# Holder_Accu.net
KiCad netlist of a schematic drawn in Altium Designer
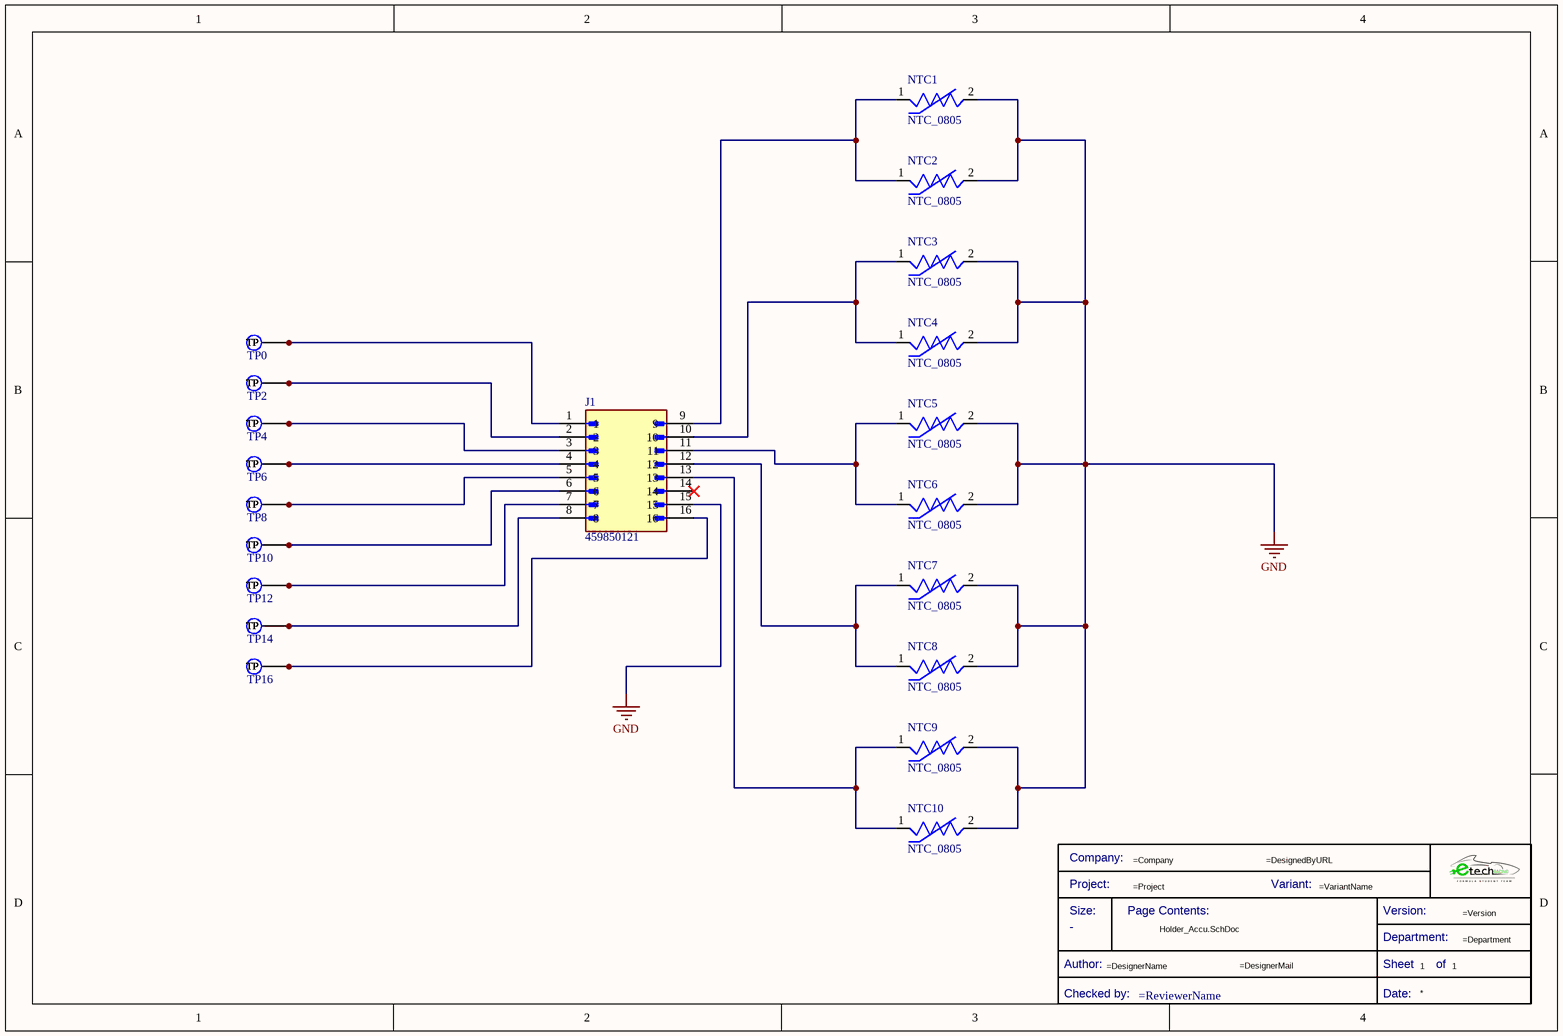
[diagram p0: Holder_Accu.SchDoc]

(export (version "E")
  (design (tool "Eeschema 10.0.6"))
  (components
    (comp (ref "*")
      (value "Title Block_template")
      (description "Standard Title Block")
      (fields
        (field (name "SIZE") "-")
        (field (name ".CREATOR") "GP")
        (field (name ".PCBCHECK") "GP")
        (field (name ".SCHCHECK") "GP")
      )
      (libsource (lib "e-Tech_Racing") (part "Title Block_template"))
    )
    (comp (ref "J1")
      (value "459850121")
      (footprint "MOLEX_459850121")
      (libsource (lib "459850121") (part "459850121"))
    )
    (comp (ref "NTC1")
      (value "NTC_0805")
      (footprint "NTC_0805")
      (description "NTC Thermistor 10k 0805 (2012 Metric)")
      (fields (field (name "MF") "TDK Corporation") (field (name "MP") "NTCG203NH103JTDS"))
      (libsource (lib "yo") (part "NTC_0805"))
    )
    (comp (ref "NTC2")
      (value "NTC_0805")
      (footprint "NTC_0805")
      (description "NTC Thermistor 10k 0805 (2012 Metric)")
      (fields (field (name "MF") "TDK Corporation") (field (name "MP") "NTCG203NH103JTDS"))
      (libsource (lib "yo") (part "NTC_0805"))
    )
    (comp (ref "NTC3")
      (value "NTC_0805")
      (footprint "NTC_0805")
      (description "NTC Thermistor 10k 0805 (2012 Metric)")
      (fields (field (name "MF") "TDK Corporation") (field (name "MP") "NTCG203NH103JTDS"))
      (libsource (lib "yo") (part "NTC_0805"))
    )
    (comp (ref "NTC4")
      (value "NTC_0805")
      (footprint "NTC_0805")
      (description "NTC Thermistor 10k 0805 (2012 Metric)")
      (fields (field (name "MF") "TDK Corporation") (field (name "MP") "NTCG203NH103JTDS"))
      (libsource (lib "yo") (part "NTC_0805"))
    )
    (comp (ref "NTC5")
      (value "NTC_0805")
      (footprint "NTC_0805")
      (description "NTC Thermistor 10k 0805 (2012 Metric)")
      (fields (field (name "MF") "TDK Corporation") (field (name "MP") "NTCG203NH103JTDS"))
      (libsource (lib "yo") (part "NTC_0805"))
    )
    (comp (ref "NTC6")
      (value "NTC_0805")
      (footprint "NTC_0805")
      (description "NTC Thermistor 10k 0805 (2012 Metric)")
      (fields (field (name "MF") "TDK Corporation") (field (name "MP") "NTCG203NH103JTDS"))
      (libsource (lib "yo") (part "NTC_0805"))
    )
    (comp (ref "NTC7")
      (value "NTC_0805")
      (footprint "NTC_0805")
      (description "NTC Thermistor 10k 0805 (2012 Metric)")
      (fields (field (name "MF") "TDK Corporation") (field (name "MP") "NTCG203NH103JTDS"))
      (libsource (lib "yo") (part "NTC_0805"))
    )
    (comp (ref "NTC8")
      (value "NTC_0805")
      (footprint "NTC_0805")
      (description "NTC Thermistor 10k 0805 (2012 Metric)")
      (fields (field (name "MF") "TDK Corporation") (field (name "MP") "NTCG203NH103JTDS"))
      (libsource (lib "yo") (part "NTC_0805"))
    )
    (comp (ref "NTC9")
      (value "NTC_0805")
      (footprint "NTC_0805")
      (description "NTC Thermistor 10k 0805 (2012 Metric)")
      (fields (field (name "MF") "TDK Corporation") (field (name "MP") "NTCG203NH103JTDS"))
      (libsource (lib "yo") (part "NTC_0805"))
    )
    (comp (ref "NTC10")
      (value "NTC_0805")
      (footprint "NTC_0805")
      (description "NTC Thermistor 10k 0805 (2012 Metric)")
      (fields (field (name "MF") "TDK Corporation") (field (name "MP") "NTCG203NH103JTDS"))
      (libsource (lib "yo") (part "NTC_0805"))
    )
    (comp (ref "TP0")
      (value "Test Point")
      (footprint "TESTPOINT_WIDE")
      (description "TestPoint 5x5mm")
      (libsource (lib "e-Tech_Racing") (part "TestPoint_Wide"))
    )
    (comp (ref "TP2")
      (value "Test Point")
      (footprint "TESTPOINT_WIDE")
      (description "TestPoint 5x5mm")
      (libsource (lib "e-Tech_Racing") (part "TestPoint_Wide"))
    )
    (comp (ref "TP4")
      (value "Test Point")
      (footprint "TESTPOINT_WIDE")
      (description "TestPoint 5x5mm")
      (libsource (lib "e-Tech_Racing") (part "TestPoint_Wide"))
    )
    (comp (ref "TP6")
      (value "Test Point")
      (footprint "TESTPOINT_WIDE")
      (description "TestPoint 5x5mm")
      (libsource (lib "e-Tech_Racing") (part "TestPoint_Wide"))
    )
    (comp (ref "TP8")
      (value "Test Point")
      (footprint "TESTPOINT_WIDE")
      (description "TestPoint 5x5mm")
      (libsource (lib "e-Tech_Racing") (part "TestPoint_Wide"))
    )
    (comp (ref "TP10")
      (value "Test Point")
      (footprint "TESTPOINT_WIDE")
      (description "TestPoint 5x5mm")
      (libsource (lib "e-Tech_Racing") (part "TestPoint_Wide"))
    )
    (comp (ref "TP12")
      (value "Test Point")
      (footprint "TESTPOINT_WIDE")
      (description "TestPoint 5x5mm")
      (libsource (lib "e-Tech_Racing") (part "TestPoint_Wide"))
    )
    (comp (ref "TP14")
      (value "Test Point")
      (footprint "TESTPOINT_WIDE")
      (description "TestPoint 5x5mm")
      (libsource (lib "e-Tech_Racing") (part "TestPoint_Wide"))
    )
    (comp (ref "TP16")
      (value "Test Point")
      (footprint "TESTPOINT_WIDE")
      (description "TestPoint 5x5mm")
      (libsource (lib "e-Tech_Racing") (part "TestPoint_Wide"))
    )
  )
  (nets
    (net (code "1") (name "GND") (class "Default")
      (node (ref "J1") (pin "15") (pinfunction "15_15") (pintype "passive"))
      (node (ref "NTC1") (pin "2") (pinfunction "2_2") (pintype "passive"))
      (node (ref "NTC10") (pin "2") (pinfunction "2_2") (pintype "passive"))
      (node (ref "NTC2") (pin "2") (pinfunction "2_2") (pintype "passive"))
      (node (ref "NTC3") (pin "2") (pinfunction "2_2") (pintype "passive"))
      (node (ref "NTC4") (pin "2") (pinfunction "2_2") (pintype "passive"))
      (node (ref "NTC5") (pin "2") (pinfunction "2_2") (pintype "passive"))
      (node (ref "NTC6") (pin "2") (pinfunction "2_2") (pintype "passive"))
      (node (ref "NTC7") (pin "2") (pinfunction "2_2") (pintype "passive"))
      (node (ref "NTC8") (pin "2") (pinfunction "2_2") (pintype "passive"))
      (node (ref "NTC9") (pin "2") (pinfunction "2_2") (pintype "passive"))
    )
    (net (code "2") (name "Net-(J1-Pad9)") (class "Default")
      (node (ref "J1") (pin "9") (pinfunction "9_9") (pintype "passive"))
      (node (ref "NTC1") (pin "1") (pinfunction "1_1") (pintype "passive"))
      (node (ref "NTC2") (pin "1") (pinfunction "1_1") (pintype "passive"))
    )
    (net (code "3") (name "Net-(J1-Pad10)") (class "Default")
      (node (ref "J1") (pin "10") (pinfunction "10_10") (pintype "passive"))
      (node (ref "NTC3") (pin "1") (pinfunction "1_1") (pintype "passive"))
      (node (ref "NTC4") (pin "1") (pinfunction "1_1") (pintype "passive"))
    )
    (net (code "4") (name "Net-(J1-Pad11)") (class "Default")
      (node (ref "J1") (pin "11") (pinfunction "11_11") (pintype "passive"))
      (node (ref "NTC5") (pin "1") (pinfunction "1_1") (pintype "passive"))
      (node (ref "NTC6") (pin "1") (pinfunction "1_1") (pintype "passive"))
    )
    (net (code "5") (name "Net-(J1-Pad12)") (class "Default")
      (node (ref "J1") (pin "12") (pinfunction "12_12") (pintype "passive"))
      (node (ref "NTC7") (pin "1") (pinfunction "1_1") (pintype "passive"))
      (node (ref "NTC8") (pin "1") (pinfunction "1_1") (pintype "passive"))
    )
    (net (code "6") (name "Net-(J1-Pad13)") (class "Default")
      (node (ref "J1") (pin "13") (pinfunction "13_13") (pintype "passive"))
      (node (ref "NTC10") (pin "1") (pinfunction "1_1") (pintype "passive"))
      (node (ref "NTC9") (pin "1") (pinfunction "1_1") (pintype "passive"))
    )
    (net (code "7") (name "Net-(TP0-TP)") (class "Default")
      (node (ref "J1") (pin "1") (pinfunction "1_1") (pintype "passive"))
      (node (ref "TP0") (pin "1") (pinfunction "TP_1") (pintype "passive"))
    )
    (net (code "8") (name "Net-(TP2-TP)") (class "Default")
      (node (ref "J1") (pin "2") (pinfunction "2_2") (pintype "passive"))
      (node (ref "TP2") (pin "1") (pinfunction "TP_1") (pintype "passive"))
    )
    (net (code "9") (name "Net-(TP4-TP)") (class "Default")
      (node (ref "J1") (pin "3") (pinfunction "3_3") (pintype "passive"))
      (node (ref "TP4") (pin "1") (pinfunction "TP_1") (pintype "passive"))
    )
    (net (code "10") (name "Net-(TP6-TP)") (class "Default")
      (node (ref "J1") (pin "4") (pinfunction "4_4") (pintype "passive"))
      (node (ref "TP6") (pin "1") (pinfunction "TP_1") (pintype "passive"))
    )
    (net (code "11") (name "Net-(TP8-TP)") (class "Default")
      (node (ref "J1") (pin "5") (pinfunction "5_5") (pintype "passive"))
      (node (ref "TP8") (pin "1") (pinfunction "TP_1") (pintype "passive"))
    )
    (net (code "12") (name "Net-(TP10-TP)") (class "Default")
      (node (ref "J1") (pin "6") (pinfunction "6_6") (pintype "passive"))
      (node (ref "TP10") (pin "1") (pinfunction "TP_1") (pintype "passive"))
    )
    (net (code "13") (name "Net-(TP12-TP)") (class "Default")
      (node (ref "J1") (pin "7") (pinfunction "7_7") (pintype "passive"))
      (node (ref "TP12") (pin "1") (pinfunction "TP_1") (pintype "passive"))
    )
    (net (code "14") (name "Net-(TP14-TP)") (class "Default")
      (node (ref "J1") (pin "8") (pinfunction "8_8") (pintype "passive"))
      (node (ref "TP14") (pin "1") (pinfunction "TP_1") (pintype "passive"))
    )
    (net (code "15") (name "Net-(TP16-TP)") (class "Default")
      (node (ref "J1") (pin "16") (pinfunction "16_16") (pintype "passive"))
      (node (ref "TP16") (pin "1") (pinfunction "TP_1") (pintype "passive"))
    )
    (net (code "16") (name "unconnected-(J1-Pad14)") (class "Default")
      (node (ref "J1") (pin "14") (pinfunction "14_14") (pintype "passive+no_connect"))
    )
  )
)
